# Controller_Core.net
KiCad netlist of a schematic drawn in Altium Designer
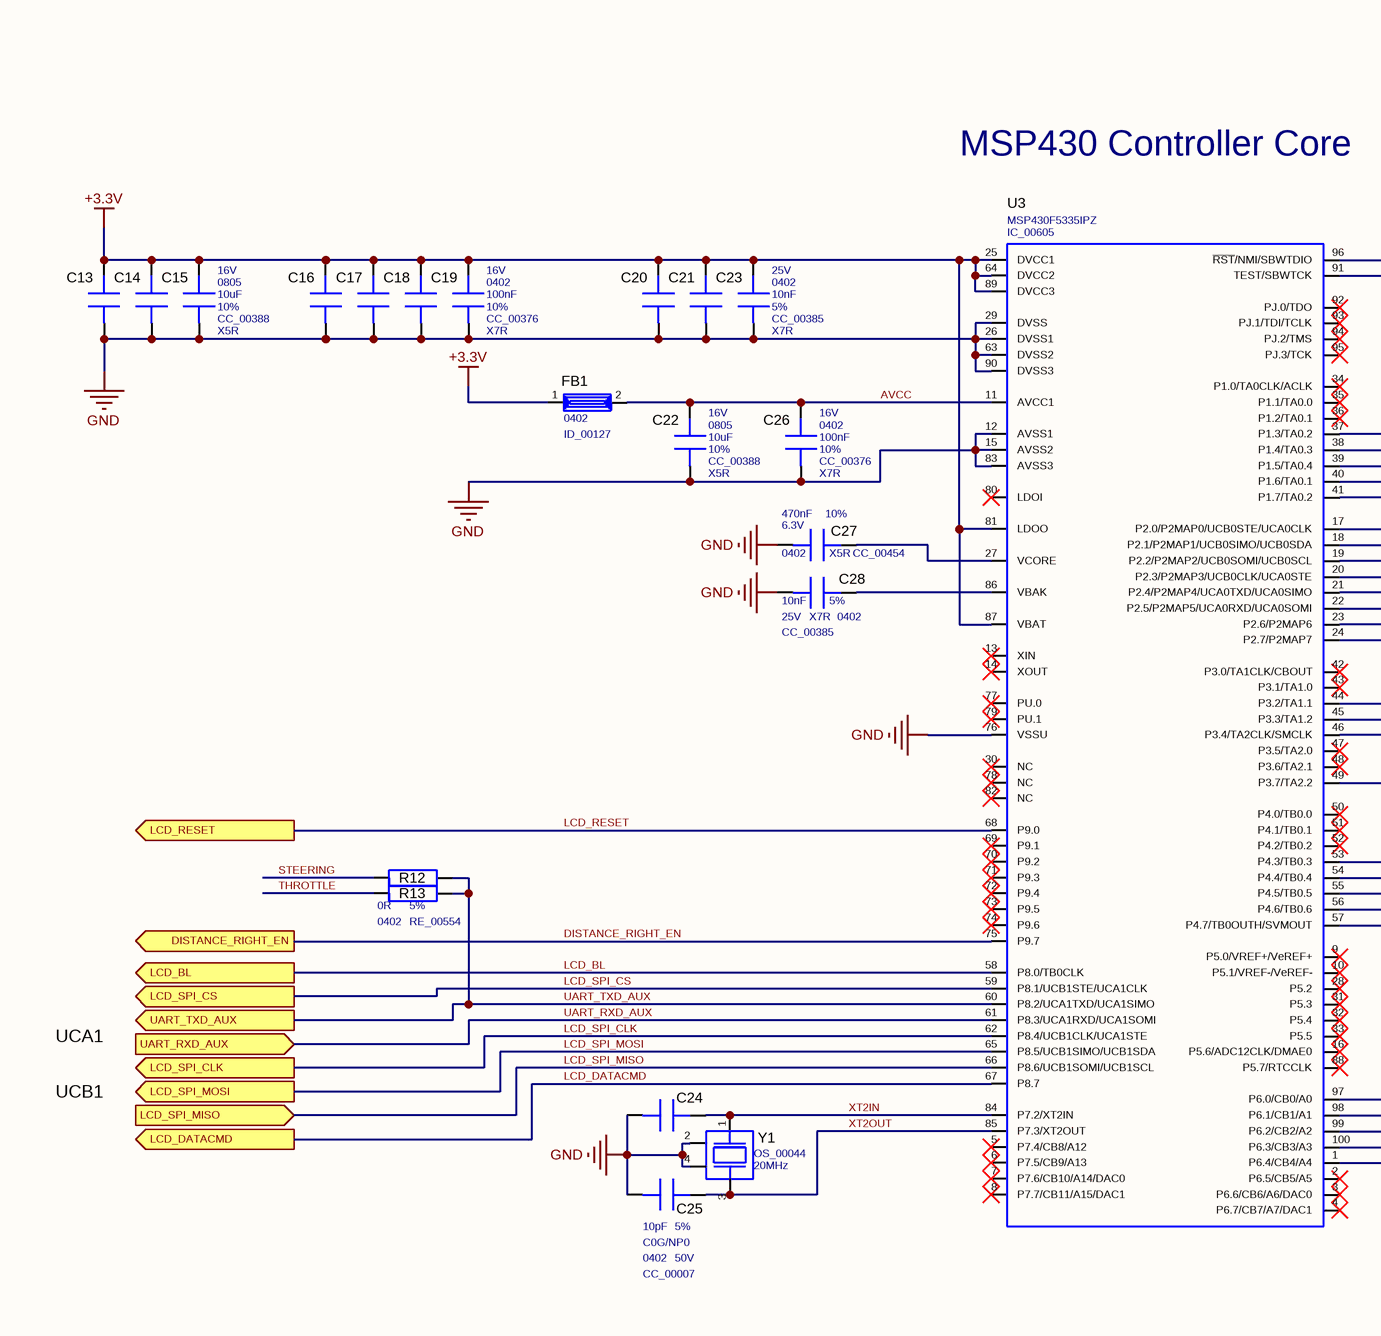
[diagram p0: Controller Core.SchDoc, left]
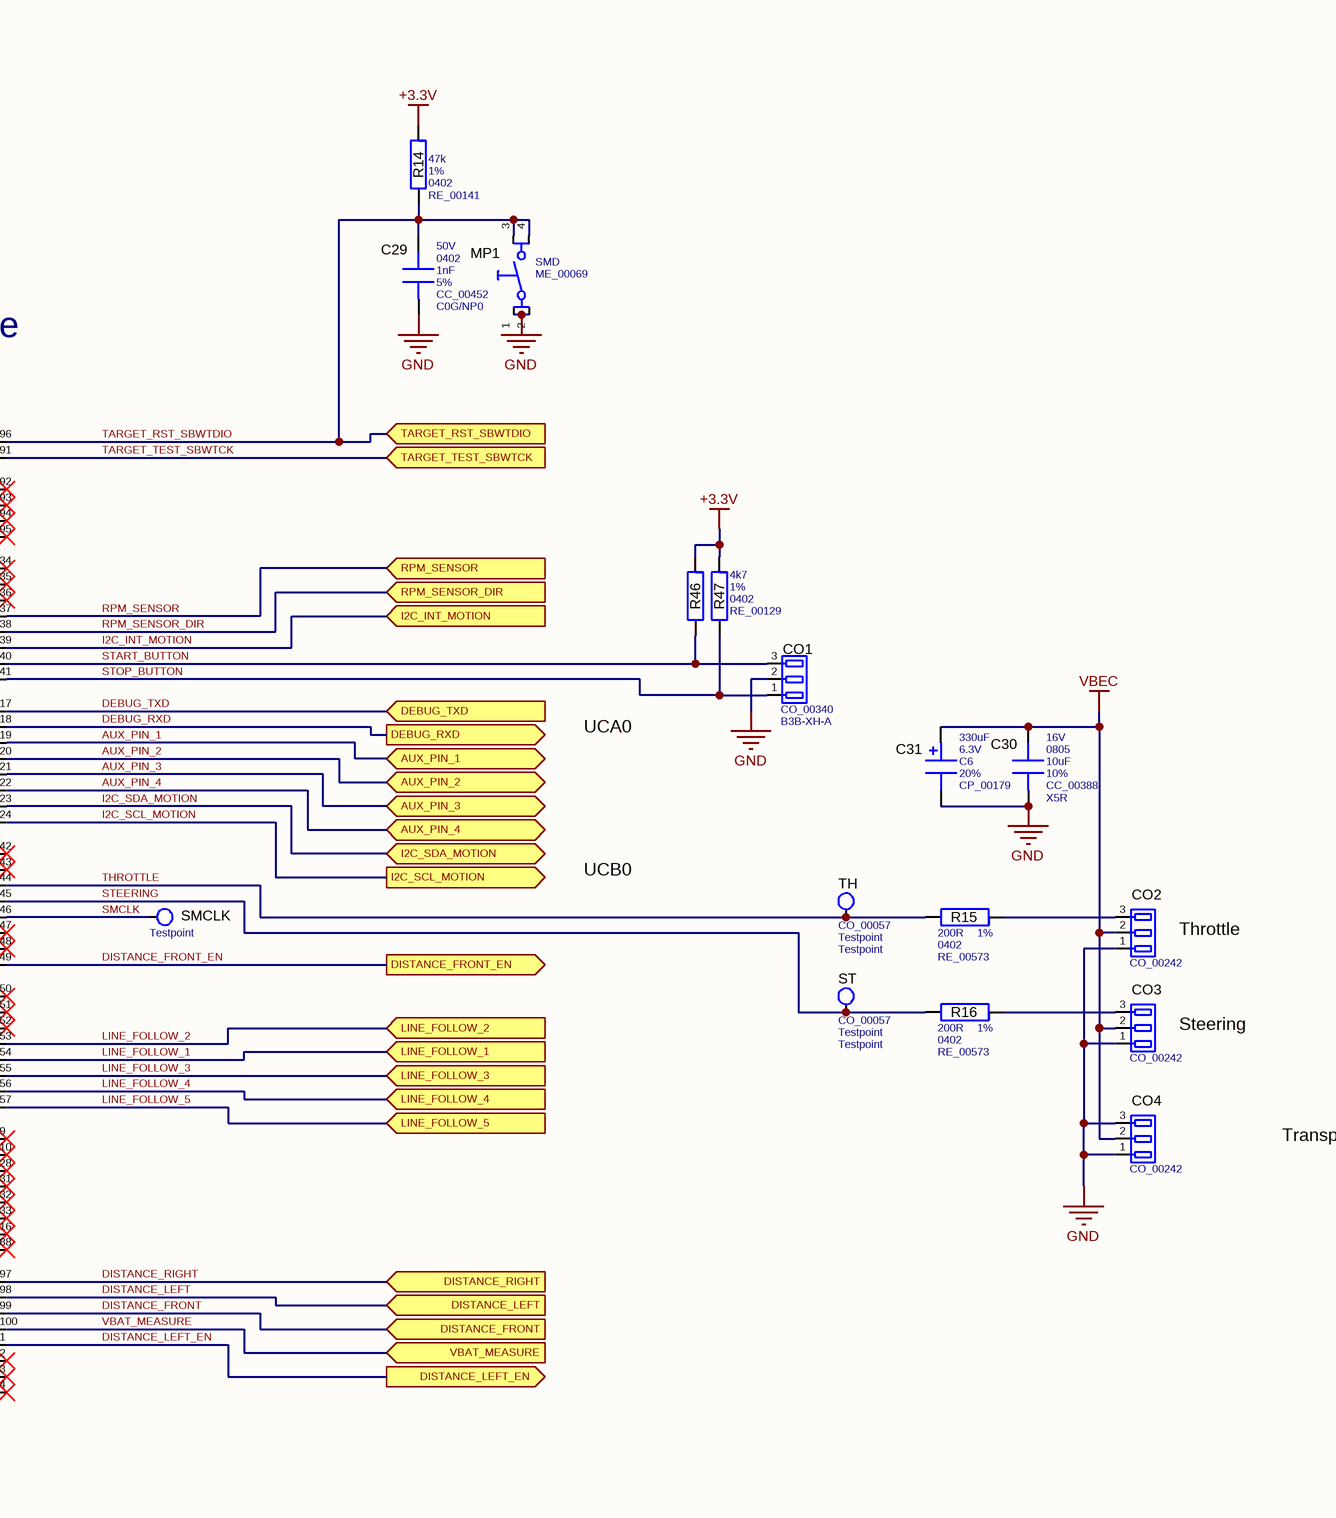
[diagram p1: Controller Core.SchDoc, right]

(export (version "E")
  (design (tool "Eeschema 10.0.6"))
  (components
    (comp (ref "C13")
      (value "capacitor")
      (footprint "CS2000x1250x1250x350x1650L")
      (fields
        (field (name "VOLTAGE") "16V")
        (field (name "TOLERANCE") "10%")
        (field (name "PART_NUMBER") "CC_00388")
        (field (name "CREATOR") "Krenn Markus")
      )
      (libsource (lib "Central Library") (part "capacitor"))
    )
    (comp (ref "C14")
      (value "capacitor")
      (footprint "CS2000x1250x1250x350x1650L")
      (fields
        (field (name "VOLTAGE") "16V")
        (field (name "TOLERANCE") "10%")
        (field (name "PART_NUMBER") "CC_00388")
        (field (name "CREATOR") "Krenn Markus")
      )
      (libsource (lib "Central Library") (part "capacitor"))
    )
    (comp (ref "C15")
      (value "capacitor")
      (footprint "CS2000x1250x1250x350x1650L")
      (fields
        (field (name "VOLTAGE") "16V")
        (field (name "PACKAGE") "0805")
        (field (name "CAPACITANCE") "10uF")
        (field (name "TOLERANCE") "10%")
        (field (name "PART_NUMBER") "CC_00388")
        (field (name "DIELECTRIC_MATERIAL") "X5R")
        (field (name "CREATOR") "Krenn Markus")
      )
      (libsource (lib "Central Library") (part "capacitor"))
    )
    (comp (ref "C16")
      (value "capacitor")
      (footprint "CS1000X500X560X250X820L")
      (fields
        (field (name "VOLTAGE") "16V")
        (field (name "TOLERANCE") "10%")
        (field (name "PART_NUMBER") "CC_00376")
        (field (name "CREATOR") "Okorn Robert")
      )
      (libsource (lib "Central Library") (part "capacitor"))
    )
    (comp (ref "C17")
      (value "capacitor")
      (footprint "CS1000X500X560X250X820L")
      (fields
        (field (name "VOLTAGE") "16V")
        (field (name "TOLERANCE") "10%")
        (field (name "PART_NUMBER") "CC_00376")
        (field (name "CREATOR") "Okorn Robert")
      )
      (libsource (lib "Central Library") (part "capacitor"))
    )
    (comp (ref "C18")
      (value "capacitor")
      (footprint "CS1000X500X560X250X820L")
      (fields
        (field (name "VOLTAGE") "16V")
        (field (name "TOLERANCE") "10%")
        (field (name "PART_NUMBER") "CC_00376")
        (field (name "CREATOR") "Okorn Robert")
      )
      (libsource (lib "Central Library") (part "capacitor"))
    )
    (comp (ref "C19")
      (value "capacitor")
      (footprint "CS1000X500X560X250X820L")
      (fields
        (field (name "VOLTAGE") "16V")
        (field (name "PACKAGE") "0402")
        (field (name "CAPACITANCE") "100nF")
        (field (name "TOLERANCE") "10%")
        (field (name "PART_NUMBER") "CC_00376")
        (field (name "DIELECTRIC_MATERIAL") "X7R")
        (field (name "CREATOR") "Okorn Robert")
      )
      (libsource (lib "Central Library") (part "capacitor"))
    )
    (comp (ref "C20")
      (value "capacitor")
      (footprint "CS1000X500X560X250X820L")
      (fields
        (field (name "VOLTAGE") "25V")
        (field (name "TOLERANCE") "5%")
        (field (name "PART_NUMBER") "CC_00385")
        (field (name "CREATOR") "Neissl Gernot")
      )
      (libsource (lib "Central Library") (part "capacitor"))
    )
    (comp (ref "C21")
      (value "capacitor")
      (footprint "CS1000X500X560X250X820L")
      (fields
        (field (name "VOLTAGE") "25V")
        (field (name "TOLERANCE") "5%")
        (field (name "PART_NUMBER") "CC_00385")
        (field (name "CREATOR") "Neissl Gernot")
      )
      (libsource (lib "Central Library") (part "capacitor"))
    )
    (comp (ref "C22")
      (value "capacitor")
      (footprint "CS2000x1250x1250x350x1650L")
      (fields
        (field (name "VOLTAGE") "16V")
        (field (name "PACKAGE") "0805")
        (field (name "CAPACITANCE") "10uF")
        (field (name "TOLERANCE") "10%")
        (field (name "PART_NUMBER") "CC_00388")
        (field (name "DIELECTRIC_MATERIAL") "X5R")
        (field (name "CREATOR") "Krenn Markus")
      )
      (libsource (lib "Central Library") (part "capacitor"))
    )
    (comp (ref "C23")
      (value "capacitor")
      (footprint "CS1000X500X560X250X820L")
      (fields
        (field (name "VOLTAGE") "25V")
        (field (name "PACKAGE") "0402")
        (field (name "CAPACITANCE") "10nF")
        (field (name "TOLERANCE") "5%")
        (field (name "PART_NUMBER") "CC_00385")
        (field (name "DIELECTRIC_MATERIAL") "X7R")
        (field (name "CREATOR") "Neissl Gernot")
      )
      (libsource (lib "Central Library") (part "capacitor"))
    )
    (comp (ref "C24")
      (value "capacitor")
      (footprint "CS1000X500X560X250X820L")
      (fields
        (field (name "VOLTAGE") "50V")
        (field (name "TOLERANCE") "5%")
        (field (name "PART_NUMBER") "CC_00007")
        (field (name "CREATOR") "Krenn Markus")
      )
      (libsource (lib "Central Library") (part "capacitor"))
    )
    (comp (ref "C25")
      (value "capacitor")
      (footprint "CS1000X500X560X250X820L")
      (fields
        (field (name "VOLTAGE") "50V")
        (field (name "PACKAGE") "0402")
        (field (name "CAPACITANCE") "10pF")
        (field (name "TOLERANCE") "5%")
        (field (name "PART_NUMBER") "CC_00007")
        (field (name "DIELECTRIC_MATERIAL") "C0G/NP0")
        (field (name "CREATOR") "Krenn Markus")
      )
      (libsource (lib "Central Library") (part "capacitor"))
    )
    (comp (ref "C26")
      (value "capacitor")
      (footprint "CS1000X500X560X250X820L")
      (fields
        (field (name "VOLTAGE") "16V")
        (field (name "PACKAGE") "0402")
        (field (name "CAPACITANCE") "100nF")
        (field (name "TOLERANCE") "10%")
        (field (name "PART_NUMBER") "CC_00376")
        (field (name "DIELECTRIC_MATERIAL") "X7R")
        (field (name "CREATOR") "Okorn Robert")
      )
      (libsource (lib "Central Library") (part "capacitor"))
    )
    (comp (ref "C27")
      (value "capacitor")
      (footprint "CS1000X500X560X250X820L")
      (fields
        (field (name "VOLTAGE") "6.3V")
        (field (name "PACKAGE") "0402")
        (field (name "CAPACITANCE") "470nF")
        (field (name "TOLERANCE") "10%")
        (field (name "PART_NUMBER") "CC_00454")
        (field (name "DIELECTRIC_MATERIAL") "X5R")
        (field (name "CREATOR") "Krenn Markus")
      )
      (libsource (lib "Central Library") (part "capacitor"))
    )
    (comp (ref "C28")
      (value "capacitor")
      (footprint "CS1000X500X560X250X820L")
      (fields
        (field (name "VOLTAGE") "25V")
        (field (name "PACKAGE") "0402")
        (field (name "CAPACITANCE") "10nF")
        (field (name "TOLERANCE") "5%")
        (field (name "PART_NUMBER") "CC_00385")
        (field (name "DIELECTRIC_MATERIAL") "X7R")
        (field (name "CREATOR") "Neissl Gernot")
      )
      (libsource (lib "Central Library") (part "capacitor"))
    )
    (comp (ref "C29")
      (value "capacitor")
      (footprint "CS1000X500X560X250X820L")
      (fields
        (field (name "VOLTAGE") "50V")
        (field (name "PACKAGE") "0402")
        (field (name "CAPACITANCE") "1nF")
        (field (name "TOLERANCE") "5%")
        (field (name "PART_NUMBER") "CC_00452")
        (field (name "DIELECTRIC_MATERIAL") "C0G/NP0")
        (field (name "CREATOR") "Krenn Markus")
      )
      (libsource (lib "Central Library") (part "capacitor"))
    )
    (comp (ref "C30")
      (value "capacitor")
      (footprint "CS2000x1250x1250x350x1650L")
      (fields
        (field (name "VOLTAGE") "16V")
        (field (name "PACKAGE") "0805")
        (field (name "CAPACITANCE") "10uF")
        (field (name "TOLERANCE") "10%")
        (field (name "PART_NUMBER") "CC_00388")
        (field (name "DIELECTRIC_MATERIAL") "X5R")
        (field (name "CREATOR") "Krenn Markus")
      )
      (libsource (lib "Central Library") (part "capacitor"))
    )
    (comp (ref "C31")
      (value "capacitor_polar")
      (footprint "CP_00179L")
      (fields
        (field (name "CAPACITANCE") "330uF")
        (field (name "VOLTAGE") "6.3V")
        (field (name "PACKAGE") "C6")
        (field (name "TOLERANCE") "20%")
        (field (name "PART_NUMBER") "CP_00179")
        (field (name "CREATOR") "Krenn Markus")
      )
      (libsource (lib "Central Library") (part "capacitor_polar"))
    )
    (comp (ref "CO1")
      (value "header1x3")
      (footprint "CO_00340N")
      (description "XH connector - Disconnectable Crimp style connectors")
      (fields
        (field (name "POWER") "0W")
        (field (name "PART_NUMBER") "CO_00340")
        (field (name "MANUFACTURER_NUMBER") "B3B-XH-A")
        (field (name "CREATOR") "Krenn Markus")
      )
      (libsource (lib "Central Library") (part "header1x3"))
    )
    (comp (ref "CO2")
      (value "header1x3")
      (footprint "CO_00242N")
      (description "THROUGH-HOLE .025\" SQ POST HEADER")
      (fields
        (field (name "POWER") "0W")
        (field (name "PART_NUMBER") "CO_00242")
        (field (name "CREATOR") "Krenn Markus")
      )
      (libsource (lib "Central Library") (part "header1x3"))
    )
    (comp (ref "CO3")
      (value "header1x3")
      (footprint "CO_00242N")
      (description "THROUGH-HOLE .025\" SQ POST HEADER")
      (fields
        (field (name "POWER") "0W")
        (field (name "PART_NUMBER") "CO_00242")
        (field (name "CREATOR") "Krenn Markus")
      )
      (libsource (lib "Central Library") (part "header1x3"))
    )
    (comp (ref "CO4")
      (value "header1x3")
      (footprint "CO_00242N")
      (description "THROUGH-HOLE .025\" SQ POST HEADER")
      (fields
        (field (name "POWER") "0W")
        (field (name "PART_NUMBER") "CO_00242")
        (field (name "CREATOR") "Krenn Markus")
      )
      (libsource (lib "Central Library") (part "header1x3"))
    )
    (comp (ref "FB1")
      (value "ferrit")
      (footprint "IS1000x500x500x200x800L")
      (fields
        (field (name "PACKAGE") "0402")
        (field (name "PART_NUMBER") "ID_00127")
        (field (name "CREATOR") "Krenn Markus")
      )
      (libsource (lib "Central Library") (part "ferrit"))
    )
    (comp (ref "MP1")
      (value "pushbutton_dpst")
      (footprint "ME_00069N")
      (fields
        (field (name "PACKAGE") "SMD")
        (field (name "PART_NUMBER") "ME_00069")
        (field (name "CREATOR") "Krenn Markus")
      )
      (libsource (lib "Central Library") (part "pushbutton_dpst"))
    )
    (comp (ref "R12")
      (value "Resistor")
      (footprint "RS1000X500X560X250X820L")
      (fields
        (field (name "TOLERANCE") "5%")
        (field (name "PART_NUMBER") "RE_00554")
        (field (name "CREATOR") "Okorn Robert")
      )
      (libsource (lib "Central Library") (part "Resistor"))
    )
    (comp (ref "R13")
      (value "Resistor")
      (footprint "RS1000X500X560X250X820L")
      (fields
        (field (name "RESISTANCE") "0R")
        (field (name "TOLERANCE") "5%")
        (field (name "PACKAGE") "0402")
        (field (name "PART_NUMBER") "RE_00554")
        (field (name "CREATOR") "Okorn Robert")
      )
      (libsource (lib "Central Library") (part "Resistor"))
    )
    (comp (ref "R14")
      (value "Resistor")
      (footprint "RS1000X500X560X250X820L")
      (fields
        (field (name "RESISTANCE") "47k")
        (field (name "TOLERANCE") "1%")
        (field (name "PACKAGE") "0402")
        (field (name "PART_NUMBER") "RE_00141")
        (field (name "CREATOR") "Krenn Markus")
      )
      (libsource (lib "Central Library") (part "Resistor"))
    )
    (comp (ref "R15")
      (value "Resistor")
      (footprint "RS1000X500X560X250X820L")
      (fields
        (field (name "RESISTANCE") "200R")
        (field (name "TOLERANCE") "1%")
        (field (name "PACKAGE") "0402")
        (field (name "PART_NUMBER") "RE_00573")
        (field (name "CREATOR") "Neissl Gernot")
      )
      (libsource (lib "Central Library") (part "Resistor"))
    )
    (comp (ref "R16")
      (value "Resistor")
      (footprint "RS1000X500X560X250X820L")
      (fields
        (field (name "RESISTANCE") "200R")
        (field (name "TOLERANCE") "1%")
        (field (name "PACKAGE") "0402")
        (field (name "PART_NUMBER") "RE_00573")
        (field (name "CREATOR") "Neissl Gernot")
      )
      (libsource (lib "Central Library") (part "Resistor"))
    )
    (comp (ref "R46")
      (value "Resistor")
      (footprint "RS1000X500X560X250X820L")
      (fields
        (field (name "TOLERANCE") "1%")
        (field (name "PART_NUMBER") "RE_00129")
        (field (name "CREATOR") "Krenn Markus")
      )
      (libsource (lib "Central Library") (part "Resistor"))
    )
    (comp (ref "R47")
      (value "Resistor")
      (footprint "RS1000X500X560X250X820L")
      (fields
        (field (name "RESISTANCE") "4k7")
        (field (name "TOLERANCE") "1%")
        (field (name "PACKAGE") "0402")
        (field (name "PART_NUMBER") "RE_00129")
        (field (name "CREATOR") "Krenn Markus")
      )
      (libsource (lib "Central Library") (part "Resistor"))
    )
    (comp (ref "SMCLK")
      (value "testpoint")
      (footprint "CO_00057N")
      (description "Testpoint 1.6mm Bohrung 1mm")
      (fields
        (field (name "PART_NUMBER") "CO_00057")
        (field (name "CONNECTOR_TYPE") "Testpoint")
        (field (name "POWER") "0W")
        (field (name "CREATOR") "Sirnik Heimo")
      )
      (libsource (lib "Central Library") (part "testpoint"))
    )
    (comp (ref "ST")
      (value "testpoint")
      (footprint "CO_00057N")
      (description "Testpoint 1.6mm Bohrung 1mm")
      (fields
        (field (name "PART_NUMBER") "CO_00057")
        (field (name "MANUFACTURER_NUMBER") "Testpoint")
        (field (name "CONNECTOR_TYPE") "Testpoint")
        (field (name "POWER") "0W")
        (field (name "CREATOR") "Sirnik Heimo")
      )
      (libsource (lib "Central Library") (part "testpoint"))
    )
    (comp (ref "TH")
      (value "testpoint")
      (footprint "CO_00057N")
      (description "Testpoint 1.6mm Bohrung 1mm")
      (fields
        (field (name "PART_NUMBER") "CO_00057")
        (field (name "MANUFACTURER_NUMBER") "Testpoint")
        (field (name "CONNECTOR_TYPE") "Testpoint")
        (field (name "POWER") "0W")
        (field (name "CREATOR") "Sirnik Heimo")
      )
      (libsource (lib "Central Library") (part "testpoint"))
    )
    (comp (ref "U3")
      (value "IC_00605")
      (footprint "IC_00605N")
      (description "MSP430F5335IPZ - MSP430F533x Mixed-Signal Microcontrollers")
      (fields
        (field (name "PART_NUMBER") "IC_00605")
        (field (name "MANUFACTURER_NUMBER") "MSP430F5335IPZ")
        (field (name "CREATOR") "Krenn Markus")
      )
      (libsource (lib "Central Library") (part "IC_00605"))
    )
    (comp (ref "Y1")
      (value "OS_00044")
      (footprint "OS_00044N")
      (description "ABM8G-20.000MHZ-4Y-T3 - ULTRA MINIATURE CERAMIC GLASS SEALED SMD CRYSTAL")
      (fields
        (field (name "TOLERANCE") "30ppm")
        (field (name "PART_NUMBER") "OS_00044")
        (field (name "NOMINAL_FREQUENCY") "20MHz")
        (field (name "CREATOR") "Krenn Markus")
      )
      (libsource (lib "Central Library") (part "OS_00044"))
    )
  )
  (nets
    (net (code "1") (name "+3.3V") (class "Default")
      (node (ref "C13") (pin "2") (pinfunction "PIN2_2") (pintype "passive"))
      (node (ref "C14") (pin "2") (pinfunction "PIN2_2") (pintype "passive"))
      (node (ref "C15") (pin "2") (pinfunction "PIN2_2") (pintype "passive"))
      (node (ref "C16") (pin "2") (pinfunction "PIN2_2") (pintype "passive"))
      (node (ref "C17") (pin "2") (pinfunction "PIN2_2") (pintype "passive"))
      (node (ref "C18") (pin "2") (pinfunction "PIN2_2") (pintype "passive"))
      (node (ref "C19") (pin "2") (pinfunction "PIN2_2") (pintype "passive"))
      (node (ref "C20") (pin "2") (pinfunction "PIN2_2") (pintype "passive"))
      (node (ref "C21") (pin "2") (pinfunction "PIN2_2") (pintype "passive"))
      (node (ref "C23") (pin "2") (pinfunction "PIN2_2") (pintype "passive"))
      (node (ref "FB1") (pin "1") (pinfunction "PIN1_1") (pintype "passive"))
      (node (ref "R14") (pin "2") (pinfunction "PIN2_2") (pintype "passive"))
      (node (ref "R46") (pin "2") (pinfunction "PIN2_2") (pintype "passive"))
      (node (ref "R47") (pin "2") (pinfunction "PIN2_2") (pintype "passive"))
      (node (ref "U3") (pin "25") (pinfunction "DVCC1_25") (pintype "passive"))
      (node (ref "U3") (pin "64") (pinfunction "DVCC2_64") (pintype "passive"))
      (node (ref "U3") (pin "81") (pinfunction "LDOO_81") (pintype "passive"))
      (node (ref "U3") (pin "87") (pinfunction "VBAT_87") (pintype "passive"))
      (node (ref "U3") (pin "89") (pinfunction "DVCC3_89") (pintype "passive"))
    )
    (net (code "2") (name "/AUX_PIN_1") (class "Default")
      (node (ref "U3") (pin "19") (pinfunction "P2.2/P2MAP2/UCB0SOMI/UCB0SCL_19") (pintype "passive"))
    )
    (net (code "3") (name "/AUX_PIN_2") (class "Default")
      (node (ref "U3") (pin "20") (pinfunction "P2.3/P2MAP3/UCB0CLK/UCA0STE_20") (pintype "passive"))
    )
    (net (code "4") (name "/AUX_PIN_3") (class "Default")
      (node (ref "U3") (pin "21") (pinfunction "P2.4/P2MAP4/UCA0TXD/UCA0SIMO_21") (pintype "passive"))
    )
    (net (code "5") (name "/AUX_PIN_4") (class "Default")
      (node (ref "U3") (pin "22") (pinfunction "P2.5/P2MAP5/UCA0RXD/UCA0SOMI_22") (pintype "passive"))
    )
    (net (code "6") (name "/AVCC") (class "Default")
      (node (ref "C22") (pin "2") (pinfunction "PIN2_2") (pintype "passive"))
      (node (ref "C26") (pin "2") (pinfunction "PIN2_2") (pintype "passive"))
      (node (ref "FB1") (pin "2") (pinfunction "PIN2_2") (pintype "passive"))
      (node (ref "U3") (pin "11") (pinfunction "AVCC1_11") (pintype "passive"))
    )
    (net (code "7") (name "/DEBUG_RXD") (class "Default")
      (node (ref "U3") (pin "18") (pinfunction "P2.1/P2MAP1/UCB0SIMO/UCB0SDA_18") (pintype "passive"))
    )
    (net (code "8") (name "/DEBUG_TXD") (class "Default")
      (node (ref "U3") (pin "17") (pinfunction "P2.0/P2MAP0/UCB0STE/UCA0CLK_17") (pintype "passive"))
    )
    (net (code "9") (name "/DISTANCE_FRONT") (class "Default")
      (node (ref "U3") (pin "99") (pinfunction "P6.2/CB2/A2_99") (pintype "passive"))
    )
    (net (code "10") (name "/DISTANCE_FRONT_EN") (class "Default")
      (node (ref "U3") (pin "49") (pinfunction "P3.7/TA2.2_49") (pintype "passive"))
    )
    (net (code "11") (name "/DISTANCE_LEFT") (class "Default")
      (node (ref "U3") (pin "98") (pinfunction "P6.1/CB1/A1_98") (pintype "passive"))
    )
    (net (code "12") (name "/DISTANCE_LEFT_EN") (class "Default")
      (node (ref "U3") (pin "1") (pinfunction "P6.4/CB4/A4_1") (pintype "passive"))
    )
    (net (code "13") (name "/DISTANCE_RIGHT") (class "Default")
      (node (ref "U3") (pin "97") (pinfunction "P6.0/CB0/A0_97") (pintype "passive"))
    )
    (net (code "14") (name "/DISTANCE_RIGHT_EN") (class "Default")
      (node (ref "U3") (pin "75") (pinfunction "P9.7_75") (pintype "passive"))
    )
    (net (code "15") (name "/I2C_INT_MOTION") (class "Default")
      (node (ref "U3") (pin "39") (pinfunction "P1.5/TA0.4_39") (pintype "passive"))
    )
    (net (code "16") (name "/I2C_SCL_MOTION") (class "Default")
      (node (ref "U3") (pin "24") (pinfunction "P2.7/P2MAP7_24") (pintype "passive"))
    )
    (net (code "17") (name "/I2C_SDA_MOTION") (class "Default")
      (node (ref "U3") (pin "23") (pinfunction "P2.6/P2MAP6_23") (pintype "passive"))
    )
    (net (code "18") (name "/LCD_BL") (class "Default")
      (node (ref "U3") (pin "58") (pinfunction "P8.0/TB0CLK_58") (pintype "passive"))
    )
    (net (code "19") (name "/LCD_DATACMD") (class "Default")
      (node (ref "U3") (pin "67") (pinfunction "P8.7_67") (pintype "passive"))
    )
    (net (code "20") (name "/LCD_RESET") (class "Default")
      (node (ref "U3") (pin "68") (pinfunction "P9.0_68") (pintype "passive"))
    )
    (net (code "21") (name "/LCD_SPI_CLK") (class "Default")
      (node (ref "U3") (pin "62") (pinfunction "P8.4/UCB1CLK/UCA1STE_62") (pintype "passive"))
    )
    (net (code "22") (name "/LCD_SPI_CS") (class "Default")
      (node (ref "U3") (pin "59") (pinfunction "P8.1/UCB1STE/UCA1CLK_59") (pintype "passive"))
    )
    (net (code "23") (name "/LCD_SPI_MISO") (class "Default")
      (node (ref "U3") (pin "66") (pinfunction "P8.6/UCB1SOMI/UCB1SCL_66") (pintype "passive"))
    )
    (net (code "24") (name "/LCD_SPI_MOSI") (class "Default")
      (node (ref "U3") (pin "65") (pinfunction "P8.5/UCB1SIMO/UCB1SDA_65") (pintype "passive"))
    )
    (net (code "25") (name "/LINE_FOLLOW_1") (class "Default")
      (node (ref "U3") (pin "54") (pinfunction "P4.4/TB0.4_54") (pintype "passive"))
    )
    (net (code "26") (name "/LINE_FOLLOW_2") (class "Default")
      (node (ref "U3") (pin "53") (pinfunction "P4.3/TB0.3_53") (pintype "passive"))
    )
    (net (code "27") (name "/LINE_FOLLOW_3") (class "Default")
      (node (ref "U3") (pin "55") (pinfunction "P4.5/TB0.5_55") (pintype "passive"))
    )
    (net (code "28") (name "/LINE_FOLLOW_4") (class "Default")
      (node (ref "U3") (pin "56") (pinfunction "P4.6/TB0.6_56") (pintype "passive"))
    )
    (net (code "29") (name "/LINE_FOLLOW_5") (class "Default")
      (node (ref "U3") (pin "57") (pinfunction "P4.7/TB0OUTH/SVMOUT_57") (pintype "passive"))
    )
    (net (code "30") (name "/RPM_SENSOR") (class "Default")
      (node (ref "U3") (pin "37") (pinfunction "P1.3/TA0.2_37") (pintype "passive"))
    )
    (net (code "31") (name "/RPM_SENSOR_DIR") (class "Default")
      (node (ref "U3") (pin "38") (pinfunction "P1.4/TA0.3_38") (pintype "passive"))
    )
    (net (code "32") (name "/SMCLK") (class "Default")
      (node (ref "SMCLK") (pin "1") (pinfunction "PIN1_1") (pintype "passive"))
      (node (ref "U3") (pin "46") (pinfunction "P3.4/TA2CLK/SMCLK_46") (pintype "passive"))
    )
    (net (code "33") (name "/START_BUTTON") (class "Default")
      (node (ref "CO1") (pin "3") (pinfunction "PIN3_3") (pintype "passive"))
      (node (ref "R46") (pin "1") (pinfunction "PIN1_1") (pintype "passive"))
      (node (ref "U3") (pin "40") (pinfunction "P1.6/TA0.1_40") (pintype "passive"))
    )
    (net (code "34") (name "/STEERING") (class "Default")
      (node (ref "R12") (pin "2") (pinfunction "PIN2_2") (pintype "passive"))
      (node (ref "R16") (pin "1") (pinfunction "PIN1_1") (pintype "passive"))
      (node (ref "ST") (pin "1") (pinfunction "PIN1_1") (pintype "passive"))
      (node (ref "U3") (pin "45") (pinfunction "P3.3/TA1.2_45") (pintype "passive"))
    )
    (net (code "35") (name "/STOP_BUTTON") (class "Default")
      (node (ref "CO1") (pin "1") (pinfunction "PIN1_1") (pintype "passive"))
      (node (ref "R47") (pin "1") (pinfunction "PIN1_1") (pintype "passive"))
      (node (ref "U3") (pin "41") (pinfunction "P1.7/TA0.2_41") (pintype "passive"))
    )
    (net (code "36") (name "/TARGET_RST_SBWTDIO") (class "Default")
      (node (ref "C29") (pin "2") (pinfunction "PIN2_2") (pintype "passive"))
      (node (ref "MP1") (pin "3") (pinfunction "PIN3_3") (pintype "passive"))
      (node (ref "MP1") (pin "4") (pinfunction "PIN4_4") (pintype "passive"))
      (node (ref "R14") (pin "1") (pinfunction "PIN1_1") (pintype "passive"))
      (node (ref "U3") (pin "96") (pinfunction "~{RST}/NMI/SBWTDIO_96") (pintype "passive"))
    )
    (net (code "37") (name "/TARGET_TEST_SBWTCK") (class "Default")
      (node (ref "U3") (pin "91") (pinfunction "TEST/SBWTCK_91") (pintype "passive"))
    )
    (net (code "38") (name "/THROTTLE") (class "Default")
      (node (ref "R13") (pin "2") (pinfunction "PIN2_2") (pintype "passive"))
      (node (ref "R15") (pin "1") (pinfunction "PIN1_1") (pintype "passive"))
      (node (ref "TH") (pin "1") (pinfunction "PIN1_1") (pintype "passive"))
      (node (ref "U3") (pin "44") (pinfunction "P3.2/TA1.1_44") (pintype "passive"))
    )
    (net (code "39") (name "/UART_RXD_AUX") (class "Default")
      (node (ref "U3") (pin "61") (pinfunction "P8.3/UCA1RXD/UCA1SOMI_61") (pintype "passive"))
    )
    (net (code "40") (name "/UART_TXD_AUX") (class "Default")
      (node (ref "R12") (pin "1") (pinfunction "PIN1_1") (pintype "passive"))
      (node (ref "R13") (pin "1") (pinfunction "PIN1_1") (pintype "passive"))
      (node (ref "U3") (pin "60") (pinfunction "P8.2/UCA1TXD/UCA1SIMO_60") (pintype "passive"))
    )
    (net (code "41") (name "/VBAT_MEASURE") (class "Default")
      (node (ref "U3") (pin "100") (pinfunction "P6.3/CB3/A3_100") (pintype "passive"))
    )
    (net (code "42") (name "/XT2IN") (class "Default")
      (node (ref "C24") (pin "2") (pinfunction "PIN2_2") (pintype "passive"))
      (node (ref "U3") (pin "84") (pinfunction "P7.2/XT2IN_84") (pintype "passive"))
      (node (ref "Y1") (pin "1") (pinfunction "PIN1_1") (pintype "passive"))
    )
    (net (code "43") (name "/XT2OUT") (class "Default")
      (node (ref "C25") (pin "2") (pinfunction "PIN2_2") (pintype "passive"))
      (node (ref "U3") (pin "85") (pinfunction "P7.3/XT2OUT_85") (pintype "passive"))
      (node (ref "Y1") (pin "3") (pinfunction "PIN3_3") (pintype "passive"))
    )
    (net (code "44") (name "GND") (class "Default")
      (node (ref "C13") (pin "1") (pinfunction "PIN1_1") (pintype "passive"))
      (node (ref "C14") (pin "1") (pinfunction "PIN1_1") (pintype "passive"))
      (node (ref "C15") (pin "1") (pinfunction "PIN1_1") (pintype "passive"))
      (node (ref "C16") (pin "1") (pinfunction "PIN1_1") (pintype "passive"))
      (node (ref "C17") (pin "1") (pinfunction "PIN1_1") (pintype "passive"))
      (node (ref "C18") (pin "1") (pinfunction "PIN1_1") (pintype "passive"))
      (node (ref "C19") (pin "1") (pinfunction "PIN1_1") (pintype "passive"))
      (node (ref "C20") (pin "1") (pinfunction "PIN1_1") (pintype "passive"))
      (node (ref "C21") (pin "1") (pinfunction "PIN1_1") (pintype "passive"))
      (node (ref "C22") (pin "1") (pinfunction "PIN1_1") (pintype "passive"))
      (node (ref "C23") (pin "1") (pinfunction "PIN1_1") (pintype "passive"))
      (node (ref "C24") (pin "1") (pinfunction "PIN1_1") (pintype "passive"))
      (node (ref "C25") (pin "1") (pinfunction "PIN1_1") (pintype "passive"))
      (node (ref "C26") (pin "1") (pinfunction "PIN1_1") (pintype "passive"))
      (node (ref "C27") (pin "1") (pinfunction "PIN1_1") (pintype "passive"))
      (node (ref "C28") (pin "1") (pinfunction "PIN1_1") (pintype "passive"))
      (node (ref "C29") (pin "1") (pinfunction "PIN1_1") (pintype "passive"))
      (node (ref "C30") (pin "1") (pinfunction "PIN1_1") (pintype "passive"))
      (node (ref "C31") (pin "2") (pinfunction "PIN2_2") (pintype "passive"))
      (node (ref "CO1") (pin "2") (pinfunction "PIN2_2") (pintype "passive"))
      (node (ref "CO2") (pin "1") (pinfunction "PIN1_1") (pintype "passive"))
      (node (ref "CO3") (pin "1") (pinfunction "PIN1_1") (pintype "passive"))
      (node (ref "CO4") (pin "1") (pinfunction "PIN1_1") (pintype "passive"))
      (node (ref "CO4") (pin "3") (pinfunction "PIN3_3") (pintype "passive"))
      (node (ref "MP1") (pin "1") (pinfunction "PIN1_1") (pintype "passive"))
      (node (ref "MP1") (pin "2") (pinfunction "PIN2_2") (pintype "passive"))
      (node (ref "U3") (pin "12") (pinfunction "AVSS1_12") (pintype "passive"))
      (node (ref "U3") (pin "15") (pinfunction "AVSS2_15") (pintype "passive"))
      (node (ref "U3") (pin "26") (pinfunction "DVSS1_26") (pintype "passive"))
      (node (ref "U3") (pin "29") (pinfunction "DVSS_29") (pintype "passive"))
      (node (ref "U3") (pin "63") (pinfunction "DVSS2_63") (pintype "passive"))
      (node (ref "U3") (pin "76") (pinfunction "VSSU_76") (pintype "passive"))
      (node (ref "U3") (pin "83") (pinfunction "AVSS3_83") (pintype "passive"))
      (node (ref "U3") (pin "90") (pinfunction "DVSS3_90") (pintype "passive"))
      (node (ref "Y1") (pin "2") (pinfunction "PIN2_2") (pintype "passive"))
      (node (ref "Y1") (pin "4") (pinfunction "PIN4_4") (pintype "passive"))
    )
    (net (code "45") (name "Net-(C27-PIN2)") (class "Default")
      (node (ref "C27") (pin "2") (pinfunction "PIN2_2") (pintype "passive"))
      (node (ref "U3") (pin "27") (pinfunction "VCORE_27") (pintype "passive"))
    )
    (net (code "46") (name "Net-(C28-PIN2)") (class "Default")
      (node (ref "C28") (pin "2") (pinfunction "PIN2_2") (pintype "passive"))
      (node (ref "U3") (pin "86") (pinfunction "VBAK_86") (pintype "passive"))
    )
    (net (code "47") (name "Net-(CO2-PIN3)") (class "Default")
      (node (ref "CO2") (pin "3") (pinfunction "PIN3_3") (pintype "passive"))
      (node (ref "R15") (pin "2") (pinfunction "PIN2_2") (pintype "passive"))
    )
    (net (code "48") (name "Net-(CO3-PIN3)") (class "Default")
      (node (ref "CO3") (pin "3") (pinfunction "PIN3_3") (pintype "passive"))
      (node (ref "R16") (pin "2") (pinfunction "PIN2_2") (pintype "passive"))
    )
    (net (code "49") (name "VBEC") (class "Default")
      (node (ref "C30") (pin "2") (pinfunction "PIN2_2") (pintype "passive"))
      (node (ref "C31") (pin "1") (pinfunction "PIN1_1") (pintype "passive"))
      (node (ref "CO2") (pin "2") (pinfunction "PIN2_2") (pintype "passive"))
      (node (ref "CO3") (pin "2") (pinfunction "PIN2_2") (pintype "passive"))
      (node (ref "CO4") (pin "2") (pinfunction "PIN2_2") (pintype "passive"))
    )
    (net (code "50") (name "unconnected-(U3-LDOI-Pad80)") (class "Default")
      (node (ref "U3") (pin "80") (pinfunction "LDOI_80") (pintype "passive+no_connect"))
    )
    (net (code "51") (name "unconnected-(U3-NC-Pad30)") (class "Default")
      (node (ref "U3") (pin "30") (pinfunction "NC_30") (pintype "passive+no_connect"))
    )
    (net (code "52") (name "unconnected-(U3-NC-Pad78)") (class "Default")
      (node (ref "U3") (pin "78") (pinfunction "NC_78") (pintype "passive+no_connect"))
    )
    (net (code "53") (name "unconnected-(U3-NC-Pad82)") (class "Default")
      (node (ref "U3") (pin "82") (pinfunction "NC_82") (pintype "passive+no_connect"))
    )
    (net (code "54") (name "unconnected-(U3-P1.0{slash}TA0CLK{slash}ACLK-Pad34)") (class "Default")
      (node (ref "U3") (pin "34") (pinfunction "P1.0/TA0CLK/ACLK_34") (pintype "passive+no_connect"))
    )
    (net (code "55") (name "unconnected-(U3-P1.1{slash}TA0.0-Pad35)") (class "Default")
      (node (ref "U3") (pin "35") (pinfunction "P1.1/TA0.0_35") (pintype "passive+no_connect"))
    )
    (net (code "56") (name "unconnected-(U3-P1.2{slash}TA0.1-Pad36)") (class "Default")
      (node (ref "U3") (pin "36") (pinfunction "P1.2/TA0.1_36") (pintype "passive+no_connect"))
    )
    (net (code "57") (name "unconnected-(U3-P3.0{slash}TA1CLK{slash}CBOUT-Pad42)") (class "Default")
      (node (ref "U3") (pin "42") (pinfunction "P3.0/TA1CLK/CBOUT_42") (pintype "passive+no_connect"))
    )
    (net (code "58") (name "unconnected-(U3-P3.1{slash}TA1.0-Pad43)") (class "Default")
      (node (ref "U3") (pin "43") (pinfunction "P3.1/TA1.0_43") (pintype "passive+no_connect"))
    )
    (net (code "59") (name "unconnected-(U3-P3.5{slash}TA2.0-Pad47)") (class "Default")
      (node (ref "U3") (pin "47") (pinfunction "P3.5/TA2.0_47") (pintype "passive+no_connect"))
    )
    (net (code "60") (name "unconnected-(U3-P3.6{slash}TA2.1-Pad48)") (class "Default")
      (node (ref "U3") (pin "48") (pinfunction "P3.6/TA2.1_48") (pintype "passive+no_connect"))
    )
    (net (code "61") (name "unconnected-(U3-P4.0{slash}TB0.0-Pad50)") (class "Default")
      (node (ref "U3") (pin "50") (pinfunction "P4.0/TB0.0_50") (pintype "passive+no_connect"))
    )
    (net (code "62") (name "unconnected-(U3-P4.1{slash}TB0.1-Pad51)") (class "Default")
      (node (ref "U3") (pin "51") (pinfunction "P4.1/TB0.1_51") (pintype "passive+no_connect"))
    )
    (net (code "63") (name "unconnected-(U3-P4.2{slash}TB0.2-Pad52)") (class "Default")
      (node (ref "U3") (pin "52") (pinfunction "P4.2/TB0.2_52") (pintype "passive+no_connect"))
    )
    (net (code "64") (name "unconnected-(U3-P5.0{slash}VREF+{slash}VeREF+-Pad9)") (class "Default")
      (node (ref "U3") (pin "9") (pinfunction "P5.0/VREF+/VeREF+_9") (pintype "passive+no_connect"))
    )
    (net (code "65") (name "unconnected-(U3-P5.1{slash}VREF-{slash}VeREF--Pad10)") (class "Default")
      (node (ref "U3") (pin "10") (pinfunction "P5.1/VREF-/VeREF-_10") (pintype "passive+no_connect"))
    )
    (net (code "66") (name "unconnected-(U3-P5.2-Pad28)") (class "Default")
      (node (ref "U3") (pin "28") (pinfunction "P5.2_28") (pintype "passive+no_connect"))
    )
    (net (code "67") (name "unconnected-(U3-P5.3-Pad31)") (class "Default")
      (node (ref "U3") (pin "31") (pinfunction "P5.3_31") (pintype "passive+no_connect"))
    )
    (net (code "68") (name "unconnected-(U3-P5.4-Pad32)") (class "Default")
      (node (ref "U3") (pin "32") (pinfunction "P5.4_32") (pintype "passive+no_connect"))
    )
    (net (code "69") (name "unconnected-(U3-P5.5-Pad33)") (class "Default")
      (node (ref "U3") (pin "33") (pinfunction "P5.5_33") (pintype "passive+no_connect"))
    )
    (net (code "70") (name "unconnected-(U3-P5.6{slash}ADC12CLK{slash}DMAE0-Pad16)") (class "Default")
      (node (ref "U3") (pin "16") (pinfunction "P5.6/ADC12CLK/DMAE0_16") (pintype "passive+no_connect"))
    )
    (net (code "71") (name "unconnected-(U3-P5.7{slash}RTCCLK-Pad88)") (class "Default")
      (node (ref "U3") (pin "88") (pinfunction "P5.7/RTCCLK_88") (pintype "passive+no_connect"))
    )
    (net (code "72") (name "unconnected-(U3-P6.5{slash}CB5{slash}A5-Pad2)") (class "Default")
      (node (ref "U3") (pin "2") (pinfunction "P6.5/CB5/A5_2") (pintype "passive+no_connect"))
    )
    (net (code "73") (name "unconnected-(U3-P6.6{slash}CB6{slash}A6{slash}DAC0-Pad3)") (class "Default")
      (node (ref "U3") (pin "3") (pinfunction "P6.6/CB6/A6/DAC0_3") (pintype "passive+no_connect"))
    )
    (net (code "74") (name "unconnected-(U3-P6.7{slash}CB7{slash}A7{slash}DAC1-Pad4)") (class "Default")
      (node (ref "U3") (pin "4") (pinfunction "P6.7/CB7/A7/DAC1_4") (pintype "passive+no_connect"))
    )
    (net (code "75") (name "unconnected-(U3-P7.4{slash}CB8{slash}A12-Pad5)") (class "Default")
      (node (ref "U3") (pin "5") (pinfunction "P7.4/CB8/A12_5") (pintype "passive+no_connect"))
    )
    (net (code "76") (name "unconnected-(U3-P7.5{slash}CB9{slash}A13-Pad6)") (class "Default")
      (node (ref "U3") (pin "6") (pinfunction "P7.5/CB9/A13_6") (pintype "passive+no_connect"))
    )
    (net (code "77") (name "unconnected-(U3-P7.6{slash}CB10{slash}A14{slash}DAC0-Pad7)") (class "Default")
      (node (ref "U3") (pin "7") (pinfunction "P7.6/CB10/A14/DAC0_7") (pintype "passive+no_connect"))
    )
    (net (code "78") (name "unconnected-(U3-P7.7{slash}CB11{slash}A15{slash}DAC1-Pad8)") (class "Default")
      (node (ref "U3") (pin "8") (pinfunction "P7.7/CB11/A15/DAC1_8") (pintype "passive+no_connect"))
    )
    (net (code "79") (name "unconnected-(U3-P9.1-Pad69)") (class "Default")
      (node (ref "U3") (pin "69") (pinfunction "P9.1_69") (pintype "passive+no_connect"))
    )
    (net (code "80") (name "unconnected-(U3-P9.2-Pad70)") (class "Default")
      (node (ref "U3") (pin "70") (pinfunction "P9.2_70") (pintype "passive+no_connect"))
    )
    (net (code "81") (name "unconnected-(U3-P9.3-Pad71)") (class "Default")
      (node (ref "U3") (pin "71") (pinfunction "P9.3_71") (pintype "passive+no_connect"))
    )
    (net (code "82") (name "unconnected-(U3-P9.4-Pad72)") (class "Default")
      (node (ref "U3") (pin "72") (pinfunction "P9.4_72") (pintype "passive+no_connect"))
    )
    (net (code "83") (name "unconnected-(U3-P9.5-Pad73)") (class "Default")
      (node (ref "U3") (pin "73") (pinfunction "P9.5_73") (pintype "passive+no_connect"))
    )
    (net (code "84") (name "unconnected-(U3-P9.6-Pad74)") (class "Default")
      (node (ref "U3") (pin "74") (pinfunction "P9.6_74") (pintype "passive+no_connect"))
    )
    (net (code "85") (name "unconnected-(U3-PJ.0{slash}TDO-Pad92)") (class "Default")
      (node (ref "U3") (pin "92") (pinfunction "PJ.0/TDO_92") (pintype "passive+no_connect"))
    )
    (net (code "86") (name "unconnected-(U3-PJ.1{slash}TDI{slash}TCLK-Pad93)") (class "Default")
      (node (ref "U3") (pin "93") (pinfunction "PJ.1/TDI/TCLK_93") (pintype "passive+no_connect"))
    )
    (net (code "87") (name "unconnected-(U3-PJ.2{slash}TMS-Pad94)") (class "Default")
      (node (ref "U3") (pin "94") (pinfunction "PJ.2/TMS_94") (pintype "passive+no_connect"))
    )
    (net (code "88") (name "unconnected-(U3-PJ.3{slash}TCK-Pad95)") (class "Default")
      (node (ref "U3") (pin "95") (pinfunction "PJ.3/TCK_95") (pintype "passive+no_connect"))
    )
    (net (code "89") (name "unconnected-(U3-PU.0-Pad77)") (class "Default")
      (node (ref "U3") (pin "77") (pinfunction "PU.0_77") (pintype "passive+no_connect"))
    )
    (net (code "90") (name "unconnected-(U3-PU.1-Pad79)") (class "Default")
      (node (ref "U3") (pin "79") (pinfunction "PU.1_79") (pintype "passive+no_connect"))
    )
    (net (code "91") (name "unconnected-(U3-XIN-Pad13)") (class "Default")
      (node (ref "U3") (pin "13") (pinfunction "XIN_13") (pintype "passive+no_connect"))
    )
    (net (code "92") (name "unconnected-(U3-XOUT-Pad14)") (class "Default")
      (node (ref "U3") (pin "14") (pinfunction "XOUT_14") (pintype "passive+no_connect"))
    )
  )
)
